# ep_project_1.net
KiCad netlist of a schematic drawn in EAGLE
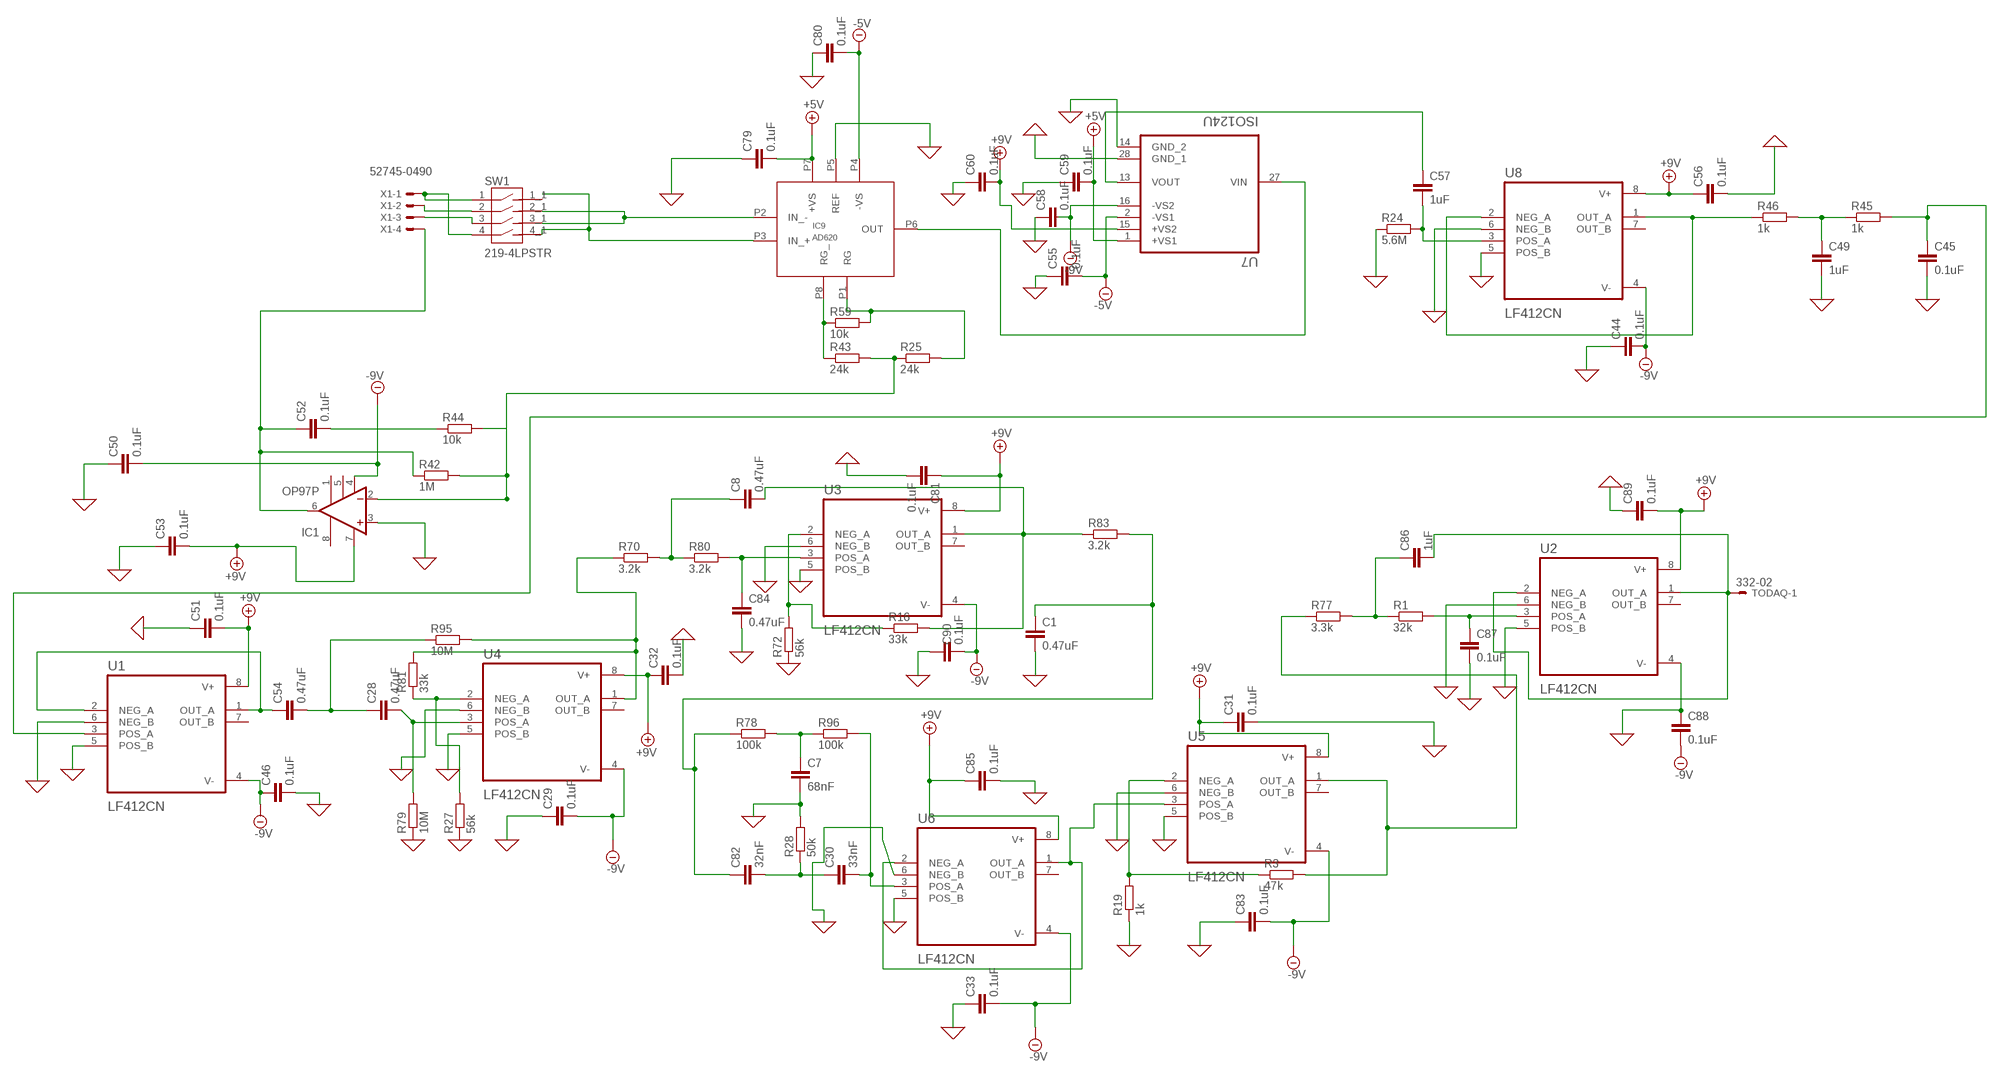
[diagram p0: schematic, sheet 1]

(export (version "E")
  (design (tool "Eeschema 10.0.6"))
  (components
    (comp (ref "C1")
      (value "0.47uF")
      (footprint "eagle-import:C025-025X050")
      (libsource (lib "eagle-import") (part "C-EU025-025X050"))
    )
    (comp (ref "C7")
      (value "68nF")
      (footprint "eagle-import:C025-025X050")
      (libsource (lib "eagle-import") (part "C-EU025-025X050"))
    )
    (comp (ref "C8")
      (value "0.47uF")
      (footprint "eagle-import:C025-025X050")
      (libsource (lib "eagle-import") (part "C-EU025-025X050"))
    )
    (comp (ref "C28")
      (value "0.47uF")
      (footprint "eagle-import:C025-025X050")
      (libsource (lib "eagle-import") (part "C-EU025-025X050"))
    )
    (comp (ref "C29")
      (value "0.1uF")
      (footprint "eagle-import:C025-025X050")
      (libsource (lib "eagle-import") (part "C-EU025-025X050"))
    )
    (comp (ref "C30")
      (value "33nF")
      (footprint "eagle-import:C025-025X050")
      (libsource (lib "eagle-import") (part "C-EU025-025X050"))
    )
    (comp (ref "C31")
      (value "0.1uF")
      (footprint "eagle-import:C025-025X050")
      (libsource (lib "eagle-import") (part "C-EU025-025X050"))
    )
    (comp (ref "C32")
      (value "0.1uF")
      (footprint "eagle-import:C025-025X050")
      (libsource (lib "eagle-import") (part "C-EU025-025X050"))
    )
    (comp (ref "C33")
      (value "0.1uF")
      (footprint "eagle-import:C025-025X050")
      (libsource (lib "eagle-import") (part "C-EU025-025X050"))
    )
    (comp (ref "C44")
      (value "0.1uF")
      (footprint "eagle-import:C025-025X050")
      (libsource (lib "eagle-import") (part "C-EU025-025X050"))
    )
    (comp (ref "C45")
      (value "0.1uF")
      (footprint "eagle-import:C025-025X050")
      (libsource (lib "eagle-import") (part "C-EU025-025X050"))
    )
    (comp (ref "C46")
      (value "0.1uF")
      (footprint "eagle-import:C025-025X050")
      (libsource (lib "eagle-import") (part "C-EU025-025X050"))
    )
    (comp (ref "C49")
      (value "1uF")
      (footprint "eagle-import:C025-025X050")
      (libsource (lib "eagle-import") (part "C-EU025-025X050"))
    )
    (comp (ref "C50")
      (value "0.1uF")
      (footprint "eagle-import:C025-025X050")
      (libsource (lib "eagle-import") (part "C-EU025-025X050"))
    )
    (comp (ref "C51")
      (value "0.1uF")
      (footprint "eagle-import:C025-025X050")
      (libsource (lib "eagle-import") (part "C-EU025-025X050"))
    )
    (comp (ref "C52")
      (value "0.1uF")
      (footprint "eagle-import:C025-025X050")
      (libsource (lib "eagle-import") (part "C-EU025-025X050"))
    )
    (comp (ref "C53")
      (value "0.1uF")
      (footprint "eagle-import:C025-025X050")
      (libsource (lib "eagle-import") (part "C-EU025-025X050"))
    )
    (comp (ref "C54")
      (value "0.47uF")
      (footprint "eagle-import:C025-025X050")
      (libsource (lib "eagle-import") (part "C-EU025-025X050"))
    )
    (comp (ref "C55")
      (value "0.1uF")
      (footprint "eagle-import:C025-025X050")
      (libsource (lib "eagle-import") (part "C-EU025-025X050"))
    )
    (comp (ref "C56")
      (value "0.1uF")
      (footprint "eagle-import:C025-025X050")
      (libsource (lib "eagle-import") (part "C-EU025-025X050"))
    )
    (comp (ref "C57")
      (value "1uF")
      (footprint "eagle-import:C025-025X050")
      (libsource (lib "eagle-import") (part "C-EU025-025X050"))
    )
    (comp (ref "C58")
      (value "0.1uF")
      (footprint "eagle-import:C025-025X050")
      (libsource (lib "eagle-import") (part "C-EU025-025X050"))
    )
    (comp (ref "C59")
      (value "0.1uF")
      (footprint "eagle-import:C025-025X050")
      (libsource (lib "eagle-import") (part "C-EU025-025X050"))
    )
    (comp (ref "C60")
      (value "0.1uF")
      (footprint "eagle-import:C025-025X050")
      (libsource (lib "eagle-import") (part "C-EU025-025X050"))
    )
    (comp (ref "C79")
      (value "0.1uF")
      (footprint "eagle-import:C025-025X050")
      (libsource (lib "eagle-import") (part "C-EU025-025X050"))
    )
    (comp (ref "C80")
      (value "0.1uF")
      (footprint "eagle-import:C025-025X050")
      (libsource (lib "eagle-import") (part "C-EU025-025X050"))
    )
    (comp (ref "C81")
      (value "0.1uF")
      (footprint "eagle-import:C025-025X050")
      (libsource (lib "eagle-import") (part "C-EU025-025X050"))
    )
    (comp (ref "C82")
      (value "32nF")
      (footprint "eagle-import:C025-025X050")
      (libsource (lib "eagle-import") (part "C-EU025-025X050"))
    )
    (comp (ref "C83")
      (value "0.1uF")
      (footprint "eagle-import:C025-025X050")
      (libsource (lib "eagle-import") (part "C-EU025-025X050"))
    )
    (comp (ref "C84")
      (value "0.47uF")
      (footprint "eagle-import:C025-025X050")
      (libsource (lib "eagle-import") (part "C-EU025-025X050"))
    )
    (comp (ref "C85")
      (value "0.1uF")
      (footprint "eagle-import:C025-025X050")
      (libsource (lib "eagle-import") (part "C-EU025-025X050"))
    )
    (comp (ref "C86")
      (value "1uF")
      (footprint "eagle-import:C025-025X050")
      (libsource (lib "eagle-import") (part "C-EU025-025X050"))
    )
    (comp (ref "C87")
      (value "0.1uF")
      (footprint "eagle-import:C025-025X050")
      (libsource (lib "eagle-import") (part "C-EU025-025X050"))
    )
    (comp (ref "C88")
      (value "0.1uF")
      (footprint "eagle-import:C025-025X050")
      (libsource (lib "eagle-import") (part "C-EU025-025X050"))
    )
    (comp (ref "C89")
      (value "0.1uF")
      (footprint "eagle-import:C025-025X050")
      (libsource (lib "eagle-import") (part "C-EU025-025X050"))
    )
    (comp (ref "C90")
      (value "0.1uF")
      (footprint "eagle-import:C025-025X050")
      (libsource (lib "eagle-import") (part "C-EU025-025X050"))
    )
    (comp (ref "IC1")
      (value "OP97P")
      (footprint "eagle-import:DIL08")
      (libsource (lib "eagle-import") (part "OP97P"))
    )
    (comp (ref "IC9")
      (value "AD620")
      (footprint "eagle-import:DIL8")
      (libsource (lib "eagle-import") (part "AD620"))
    )
    (comp (ref "R1")
      (value "32k")
      (footprint "eagle-import:0204_7")
      (libsource (lib "eagle-import") (part "R-EU_0204/7"))
    )
    (comp (ref "R3")
      (value "47k")
      (footprint "eagle-import:0204_7")
      (libsource (lib "eagle-import") (part "R-EU_0204/7"))
    )
    (comp (ref "R16")
      (value "33k")
      (footprint "eagle-import:VTA55")
      (libsource (lib "eagle-import") (part "R-EU_VTA55"))
    )
    (comp (ref "R19")
      (value "1k")
      (footprint "eagle-import:0204_7")
      (libsource (lib "eagle-import") (part "R-EU_0204/7"))
    )
    (comp (ref "R24")
      (value "5.6M")
      (footprint "eagle-import:0204_7")
      (libsource (lib "eagle-import") (part "R-EU_0204/7"))
    )
    (comp (ref "R25")
      (value "24k")
      (footprint "eagle-import:0204_7")
      (libsource (lib "eagle-import") (part "R-EU_0204/7"))
    )
    (comp (ref "R27")
      (value "56k")
      (footprint "eagle-import:0204_7")
      (libsource (lib "eagle-import") (part "R-EU_0204/7"))
    )
    (comp (ref "R28")
      (value "50k")
      (footprint "eagle-import:0204_7")
      (libsource (lib "eagle-import") (part "R-EU_0204/7"))
    )
    (comp (ref "R42")
      (value "1M")
      (footprint "eagle-import:0204_7")
      (libsource (lib "eagle-import") (part "R-EU_0204/7"))
    )
    (comp (ref "R43")
      (value "24k")
      (footprint "eagle-import:0204_7")
      (libsource (lib "eagle-import") (part "R-EU_0204/7"))
    )
    (comp (ref "R44")
      (value "10k")
      (footprint "eagle-import:0204_7")
      (libsource (lib "eagle-import") (part "R-EU_0204/7"))
    )
    (comp (ref "R45")
      (value "1k")
      (footprint "eagle-import:0204_7")
      (libsource (lib "eagle-import") (part "R-EU_0204/7"))
    )
    (comp (ref "R46")
      (value "1k")
      (footprint "eagle-import:0204_7")
      (libsource (lib "eagle-import") (part "R-EU_0204/7"))
    )
    (comp (ref "R59")
      (value "10k")
      (footprint "eagle-import:0204_7")
      (libsource (lib "eagle-import") (part "R-EU_0204/7"))
    )
    (comp (ref "R70")
      (value "3.2k")
      (footprint "eagle-import:0204_7")
      (libsource (lib "eagle-import") (part "R-EU_0204/7"))
    )
    (comp (ref "R72")
      (value "56k")
      (footprint "eagle-import:0204_7")
      (libsource (lib "eagle-import") (part "R-EU_0204/7"))
    )
    (comp (ref "R77")
      (value "3.3k")
      (footprint "eagle-import:0204_7")
      (libsource (lib "eagle-import") (part "R-EU_0204/7"))
    )
    (comp (ref "R78")
      (value "100k")
      (footprint "eagle-import:0204_7")
      (libsource (lib "eagle-import") (part "R-EU_0204/7"))
    )
    (comp (ref "R79")
      (value "10M")
      (footprint "eagle-import:0204_7")
      (libsource (lib "eagle-import") (part "R-EU_0204/7"))
    )
    (comp (ref "R80")
      (value "3.2k")
      (footprint "eagle-import:0204_7")
      (libsource (lib "eagle-import") (part "R-EU_0204/7"))
    )
    (comp (ref "R81")
      (value "33k")
      (footprint "eagle-import:0204_7")
      (libsource (lib "eagle-import") (part "R-EU_0204/7"))
    )
    (comp (ref "R83")
      (value "3.2k")
      (footprint "eagle-import:0204_7")
      (libsource (lib "eagle-import") (part "R-EU_0204/7"))
    )
    (comp (ref "R95")
      (value "10M")
      (footprint "eagle-import:0204_7")
      (libsource (lib "eagle-import") (part "R-EU_0204/7"))
    )
    (comp (ref "R96")
      (value "100k")
      (footprint "eagle-import:0204_7")
      (libsource (lib "eagle-import") (part "R-EU_0204/7"))
    )
    (comp (ref "SW1")
      (value "219-4LPSTR")
      (footprint "eagle-import:SW_219-4LPSTR")
      (fields (field (name "MF") "CTS Electrocomponents"))
      (libsource (lib "eagle-import") (part "219-4LPSTR"))
    )
    (comp (ref "TODAQ")
      (value "332-02")
      (footprint "eagle-import:332-02")
      (libsource (lib "eagle-import") (part "332-02"))
    )
    (comp (ref "U1")
      (value "LF412CN")
      (footprint "eagle-import:DIP794W45P254L959H508Q8")
      (fields (field (name "MF") "Texas Instruments"))
      (libsource (lib "eagle-import") (part "LF412CN"))
    )
    (comp (ref "U2")
      (value "LF412CN")
      (footprint "eagle-import:DIP794W45P254L959H508Q8")
      (fields (field (name "MF") "Texas Instruments"))
      (libsource (lib "eagle-import") (part "LF412CN"))
    )
    (comp (ref "U3")
      (value "LF412CN")
      (footprint "eagle-import:DIP794W45P254L959H508Q8")
      (fields (field (name "MF") "Texas Instruments"))
      (libsource (lib "eagle-import") (part "LF412CN"))
    )
    (comp (ref "U4")
      (value "LF412CN")
      (footprint "eagle-import:DIP794W45P254L959H508Q8")
      (fields (field (name "MF") "Texas Instruments"))
      (libsource (lib "eagle-import") (part "LF412CN"))
    )
    (comp (ref "U5")
      (value "LF412CN")
      (footprint "eagle-import:DIP794W45P254L959H508Q8")
      (fields (field (name "MF") "Texas Instruments"))
      (libsource (lib "eagle-import") (part "LF412CN"))
    )
    (comp (ref "U6")
      (value "LF412CN")
      (footprint "eagle-import:DIP794W45P254L959H508Q8")
      (fields (field (name "MF") "Texas Instruments"))
      (libsource (lib "eagle-import") (part "LF412CN"))
    )
    (comp (ref "U7")
      (value "ISO124U")
      (footprint "eagle-import:SOIC127P1033X265-8N")
      (fields (field (name "MF") "Texas Instruments"))
      (libsource (lib "eagle-import") (part "ISO124U"))
    )
    (comp (ref "U8")
      (value "LF412CN")
      (footprint "eagle-import:DIP794W45P254L959H508Q8")
      (fields (field (name "MF") "Texas Instruments"))
      (libsource (lib "eagle-import") (part "LF412CN"))
    )
    (comp (ref "X1")
      (value "52745-0490")
      (footprint "eagle-import:52745-0490")
      (fields (field (name "MF") "MOLEX"))
      (libsource (lib "eagle-import") (part "52745-0490"))
    )
  )
  (nets
    (net (code "1") (name "+5V") (class "Default")
      (node (ref "C59") (pin "2") (pinfunction "2_2") (pintype "passive"))
      (node (ref "C79") (pin "2") (pinfunction "2_2") (pintype "passive"))
      (node (ref "IC9") (pin "P7") (pinfunction "+VS_P7") (pintype "power_in"))
      (node (ref "U7") (pin "1") (pinfunction "+VS1_1") (pintype "power_in"))
    )
    (net (code "2") (name "+9V") (class "Default")
      (node (ref "C31") (pin "1") (pinfunction "1_1") (pintype "passive"))
      (node (ref "C32") (pin "1") (pinfunction "1_1") (pintype "passive"))
      (node (ref "C51") (pin "2") (pinfunction "2_2") (pintype "passive"))
      (node (ref "C53") (pin "2") (pinfunction "2_2") (pintype "passive"))
      (node (ref "C56") (pin "1") (pinfunction "1_1") (pintype "passive"))
      (node (ref "C60") (pin "2") (pinfunction "2_2") (pintype "passive"))
      (node (ref "C81") (pin "1") (pinfunction "1_1") (pintype "passive"))
      (node (ref "C85") (pin "1") (pinfunction "1_1") (pintype "passive"))
      (node (ref "C89") (pin "2") (pinfunction "2_2") (pintype "passive"))
      (node (ref "IC1") (pin "7") (pinfunction "V+_7") (pintype "power_in"))
      (node (ref "U1") (pin "8") (pinfunction "V+_8") (pintype "power_in"))
      (node (ref "U2") (pin "8") (pinfunction "V+_8") (pintype "power_in"))
      (node (ref "U3") (pin "8") (pinfunction "V+_8") (pintype "power_in"))
      (node (ref "U4") (pin "8") (pinfunction "V+_8") (pintype "power_in"))
      (node (ref "U5") (pin "8") (pinfunction "V+_8") (pintype "power_in"))
      (node (ref "U6") (pin "8") (pinfunction "V+_8") (pintype "power_in"))
      (node (ref "U7") (pin "15") (pinfunction "+VS2_15") (pintype "power_in"))
      (node (ref "U8") (pin "8") (pinfunction "V+_8") (pintype "power_in"))
    )
    (net (code "3") (name "-5V") (class "Default")
      (node (ref "C55") (pin "2") (pinfunction "2_2") (pintype "passive"))
      (node (ref "C80") (pin "2") (pinfunction "2_2") (pintype "passive"))
      (node (ref "IC9") (pin "P4") (pinfunction "-VS_P4") (pintype "power_in"))
      (node (ref "U7") (pin "2") (pinfunction "-VS1_2") (pintype "power_in"))
    )
    (net (code "4") (name "-9V") (class "Default")
      (node (ref "C29") (pin "2") (pinfunction "2_2") (pintype "passive"))
      (node (ref "C33") (pin "2") (pinfunction "2_2") (pintype "passive"))
      (node (ref "C44") (pin "2") (pinfunction "2_2") (pintype "passive"))
      (node (ref "C46") (pin "1") (pinfunction "1_1") (pintype "passive"))
      (node (ref "C50") (pin "2") (pinfunction "2_2") (pintype "passive"))
      (node (ref "C58") (pin "2") (pinfunction "2_2") (pintype "passive"))
      (node (ref "C83") (pin "2") (pinfunction "2_2") (pintype "passive"))
      (node (ref "C88") (pin "2") (pinfunction "2_2") (pintype "passive"))
      (node (ref "C90") (pin "2") (pinfunction "2_2") (pintype "passive"))
      (node (ref "IC1") (pin "4") (pinfunction "V-_4") (pintype "power_in"))
      (node (ref "U1") (pin "4") (pinfunction "V-_4") (pintype "power_in"))
      (node (ref "U3") (pin "4") (pinfunction "V-_4") (pintype "power_in"))
      (node (ref "U4") (pin "4") (pinfunction "V-_4") (pintype "power_in"))
      (node (ref "U5") (pin "4") (pinfunction "V-_4") (pintype "power_in"))
      (node (ref "U6") (pin "4") (pinfunction "V-_4") (pintype "power_in"))
      (node (ref "U7") (pin "16") (pinfunction "-VS2_16") (pintype "power_in"))
      (node (ref "U8") (pin "4") (pinfunction "V-_4") (pintype "power_in"))
    )
    (net (code "5") (name "0") (class "Default")
      (node (ref "C1") (pin "2") (pinfunction "2_2") (pintype "passive"))
      (node (ref "C29") (pin "1") (pinfunction "1_1") (pintype "passive"))
      (node (ref "C31") (pin "2") (pinfunction "2_2") (pintype "passive"))
      (node (ref "C32") (pin "2") (pinfunction "2_2") (pintype "passive"))
      (node (ref "C33") (pin "1") (pinfunction "1_1") (pintype "passive"))
      (node (ref "C44") (pin "1") (pinfunction "1_1") (pintype "passive"))
      (node (ref "C45") (pin "2") (pinfunction "2_2") (pintype "passive"))
      (node (ref "C46") (pin "2") (pinfunction "2_2") (pintype "passive"))
      (node (ref "C49") (pin "2") (pinfunction "2_2") (pintype "passive"))
      (node (ref "C50") (pin "1") (pinfunction "1_1") (pintype "passive"))
      (node (ref "C51") (pin "1") (pinfunction "1_1") (pintype "passive"))
      (node (ref "C53") (pin "1") (pinfunction "1_1") (pintype "passive"))
      (node (ref "C55") (pin "1") (pinfunction "1_1") (pintype "passive"))
      (node (ref "C56") (pin "2") (pinfunction "2_2") (pintype "passive"))
      (node (ref "C58") (pin "1") (pinfunction "1_1") (pintype "passive"))
      (node (ref "C59") (pin "1") (pinfunction "1_1") (pintype "passive"))
      (node (ref "C60") (pin "1") (pinfunction "1_1") (pintype "passive"))
      (node (ref "C7") (pin "2") (pinfunction "2_2") (pintype "passive"))
      (node (ref "C79") (pin "1") (pinfunction "1_1") (pintype "passive"))
      (node (ref "C80") (pin "1") (pinfunction "1_1") (pintype "passive"))
      (node (ref "C81") (pin "2") (pinfunction "2_2") (pintype "passive"))
      (node (ref "C83") (pin "1") (pinfunction "1_1") (pintype "passive"))
      (node (ref "C84") (pin "2") (pinfunction "2_2") (pintype "passive"))
      (node (ref "C85") (pin "2") (pinfunction "2_2") (pintype "passive"))
      (node (ref "C87") (pin "2") (pinfunction "2_2") (pintype "passive"))
      (node (ref "C88") (pin "1") (pinfunction "1_1") (pintype "passive"))
      (node (ref "C89") (pin "1") (pinfunction "1_1") (pintype "passive"))
      (node (ref "C90") (pin "1") (pinfunction "1_1") (pintype "passive"))
      (node (ref "IC1") (pin "3") (pinfunction "+IN_3") (pintype "input"))
      (node (ref "IC9") (pin "P5") (pinfunction "REF_P5") (pintype "power_in"))
      (node (ref "R19") (pin "1") (pinfunction "1_1") (pintype "passive"))
      (node (ref "R24") (pin "1") (pinfunction "1_1") (pintype "passive"))
      (node (ref "R27") (pin "1") (pinfunction "1_1") (pintype "passive"))
      (node (ref "R28") (pin "2") (pinfunction "2_2") (pintype "passive"))
      (node (ref "R72") (pin "1") (pinfunction "1_1") (pintype "passive"))
      (node (ref "R79") (pin "1") (pinfunction "1_1") (pintype "passive"))
      (node (ref "U1") (pin "5") (pinfunction "POS_B_5") (pintype "input"))
      (node (ref "U1") (pin "6") (pinfunction "NEG_B_6") (pintype "input"))
      (node (ref "U2") (pin "4") (pinfunction "V-_4") (pintype "power_in"))
      (node (ref "U2") (pin "5") (pinfunction "POS_B_5") (pintype "input"))
      (node (ref "U2") (pin "6") (pinfunction "NEG_B_6") (pintype "input"))
      (node (ref "U3") (pin "5") (pinfunction "POS_B_5") (pintype "input"))
      (node (ref "U3") (pin "6") (pinfunction "NEG_B_6") (pintype "input"))
      (node (ref "U4") (pin "5") (pinfunction "POS_B_5") (pintype "input"))
      (node (ref "U4") (pin "6") (pinfunction "NEG_B_6") (pintype "input"))
      (node (ref "U5") (pin "5") (pinfunction "POS_B_5") (pintype "input"))
      (node (ref "U5") (pin "6") (pinfunction "NEG_B_6") (pintype "input"))
      (node (ref "U6") (pin "5") (pinfunction "POS_B_5") (pintype "input"))
      (node (ref "U6") (pin "6") (pinfunction "NEG_B_6") (pintype "input"))
      (node (ref "U7") (pin "14") (pinfunction "GND_2_14") (pintype "power_in"))
      (node (ref "U7") (pin "28") (pinfunction "GND_1_28") (pintype "power_in"))
      (node (ref "U8") (pin "5") (pinfunction "POS_B_5") (pintype "input"))
      (node (ref "U8") (pin "6") (pinfunction "NEG_B_6") (pintype "input"))
    )
    (net (code "6") (name "Net-(C1-Pad1)") (class "Default")
      (node (ref "C1") (pin "1") (pinfunction "1_1") (pintype "passive"))
      (node (ref "C82") (pin "1") (pinfunction "1_1") (pintype "passive"))
      (node (ref "R78") (pin "1") (pinfunction "1_1") (pintype "passive"))
      (node (ref "R83") (pin "2") (pinfunction "2_2") (pintype "passive"))
    )
    (net (code "7") (name "Net-(C7-Pad1)") (class "Default")
      (node (ref "C7") (pin "1") (pinfunction "1_1") (pintype "passive"))
      (node (ref "R78") (pin "2") (pinfunction "2_2") (pintype "passive"))
      (node (ref "R96") (pin "1") (pinfunction "1_1") (pintype "passive"))
    )
    (net (code "8") (name "Net-(C8-Pad1)") (class "Default")
      (node (ref "C8") (pin "1") (pinfunction "1_1") (pintype "passive"))
      (node (ref "R70") (pin "2") (pinfunction "2_2") (pintype "passive"))
      (node (ref "R80") (pin "1") (pinfunction "1_1") (pintype "passive"))
    )
    (net (code "9") (name "Net-(C28-Pad1)") (class "Default")
      (node (ref "C28") (pin "1") (pinfunction "1_1") (pintype "passive"))
      (node (ref "C54") (pin "2") (pinfunction "2_2") (pintype "passive"))
      (node (ref "R95") (pin "1") (pinfunction "1_1") (pintype "passive"))
    )
    (net (code "10") (name "Net-(C30-Pad1)") (class "Default")
      (node (ref "C30") (pin "1") (pinfunction "1_1") (pintype "passive"))
      (node (ref "C82") (pin "2") (pinfunction "2_2") (pintype "passive"))
      (node (ref "R28") (pin "1") (pinfunction "1_1") (pintype "passive"))
    )
    (net (code "11") (name "Net-(C49-Pad1)") (class "Default")
      (node (ref "C49") (pin "1") (pinfunction "1_1") (pintype "passive"))
      (node (ref "R45") (pin "1") (pinfunction "1_1") (pintype "passive"))
      (node (ref "R46") (pin "2") (pinfunction "2_2") (pintype "passive"))
    )
    (net (code "12") (name "Net-(C52-Pad2)") (class "Default")
      (node (ref "C52") (pin "2") (pinfunction "2_2") (pintype "passive"))
      (node (ref "R44") (pin "1") (pinfunction "1_1") (pintype "passive"))
    )
    (net (code "13") (name "Net-(C86-Pad1)") (class "Default")
      (node (ref "C86") (pin "1") (pinfunction "1_1") (pintype "passive"))
      (node (ref "R1") (pin "1") (pinfunction "1_1") (pintype "passive"))
      (node (ref "R77") (pin "2") (pinfunction "2_2") (pintype "passive"))
    )
    (net (code "14") (name "Net-(IC1--IN)") (class "Default")
      (node (ref "IC1") (pin "2") (pinfunction "-IN_2") (pintype "input"))
      (node (ref "R25") (pin "1") (pinfunction "1_1") (pintype "passive"))
      (node (ref "R42") (pin "2") (pinfunction "2_2") (pintype "passive"))
      (node (ref "R43") (pin "2") (pinfunction "2_2") (pintype "passive"))
      (node (ref "R44") (pin "2") (pinfunction "2_2") (pintype "passive"))
    )
    (net (code "15") (name "Net-(IC1-OUT)") (class "Default")
      (node (ref "C52") (pin "1") (pinfunction "1_1") (pintype "passive"))
      (node (ref "IC1") (pin "6") (pinfunction "OUT_6") (pintype "output"))
      (node (ref "R42") (pin "1") (pinfunction "1_1") (pintype "passive"))
      (node (ref "X1") (pin "4") (pinfunction "S_4") (pintype "passive"))
    )
    (net (code "16") (name "Net-(IC9-IN_+)") (class "Default")
      (node (ref "IC9") (pin "P3") (pinfunction "IN_+_P3") (pintype "input"))
      (node (ref "SW1") (pin "4_1") (pinfunction "4_1_4_1") (pintype "passive"))
    )
    (net (code "17") (name "Net-(IC9-IN_-)") (class "Default")
      (node (ref "IC9") (pin "P2") (pinfunction "IN_-_P2") (pintype "input"))
      (node (ref "SW1") (pin "2_1") (pinfunction "2_1_2_1") (pintype "passive"))
      (node (ref "SW1") (pin "3_1") (pinfunction "3_1_3_1") (pintype "passive"))
    )
    (net (code "18") (name "Net-(IC9-OUT)") (class "Default")
      (node (ref "IC9") (pin "P6") (pinfunction "OUT_P6") (pintype "output"))
      (node (ref "U7") (pin "27") (pinfunction "VIN_27") (pintype "input"))
    )
    (net (code "19") (name "Net-(IC9-RG)") (class "Default")
      (node (ref "IC9") (pin "P1") (pinfunction "RG_P1") (pintype "input"))
      (node (ref "R25") (pin "2") (pinfunction "2_2") (pintype "passive"))
      (node (ref "R59") (pin "2") (pinfunction "2_2") (pintype "passive"))
    )
    (net (code "20") (name "Net-(IC9-RG_)") (class "Default")
      (node (ref "IC9") (pin "P8") (pinfunction "RG__P8") (pintype "input"))
      (node (ref "R43") (pin "1") (pinfunction "1_1") (pintype "passive"))
      (node (ref "R59") (pin "1") (pinfunction "1_1") (pintype "passive"))
    )
    (net (code "21") (name "Net-(TODAQA-S)") (class "Default")
      (node (ref "C86") (pin "2") (pinfunction "2_2") (pintype "passive"))
      (node (ref "TODAQ") (pin "1") (pinfunction "S_1") (pintype "passive"))
      (node (ref "U2") (pin "1") (pinfunction "OUT_A_1") (pintype "output"))
      (node (ref "U2") (pin "2") (pinfunction "NEG_A_2") (pintype "input"))
    )
    (net (code "22") (name "Net-(U1-NEG_A)") (class "Default")
      (node (ref "C54") (pin "1") (pinfunction "1_1") (pintype "passive"))
      (node (ref "U1") (pin "1") (pinfunction "OUT_A_1") (pintype "output"))
      (node (ref "U1") (pin "2") (pinfunction "NEG_A_2") (pintype "input"))
    )
    (net (code "23") (name "Net-(U1-POS_A)") (class "Default")
      (node (ref "C45") (pin "1") (pinfunction "1_1") (pintype "passive"))
      (node (ref "R45") (pin "2") (pinfunction "2_2") (pintype "passive"))
      (node (ref "U1") (pin "3") (pinfunction "POS_A_3") (pintype "input"))
    )
    (net (code "24") (name "Net-(U2-POS_A)") (class "Default")
      (node (ref "C87") (pin "1") (pinfunction "1_1") (pintype "passive"))
      (node (ref "R1") (pin "2") (pinfunction "2_2") (pintype "passive"))
      (node (ref "U2") (pin "3") (pinfunction "POS_A_3") (pintype "input"))
    )
    (net (code "25") (name "Net-(U3-NEG_A)") (class "Default")
      (node (ref "R16") (pin "1") (pinfunction "1_1") (pintype "passive"))
      (node (ref "R72") (pin "2") (pinfunction "2_2") (pintype "passive"))
      (node (ref "U3") (pin "2") (pinfunction "NEG_A_2") (pintype "input"))
    )
    (net (code "26") (name "Net-(U3-OUT_A)") (class "Default")
      (node (ref "C8") (pin "2") (pinfunction "2_2") (pintype "passive"))
      (node (ref "R16") (pin "2") (pinfunction "2_2") (pintype "passive"))
      (node (ref "R83") (pin "1") (pinfunction "1_1") (pintype "passive"))
      (node (ref "U3") (pin "1") (pinfunction "OUT_A_1") (pintype "output"))
    )
    (net (code "27") (name "Net-(U3-POS_A)") (class "Default")
      (node (ref "C84") (pin "1") (pinfunction "1_1") (pintype "passive"))
      (node (ref "R80") (pin "2") (pinfunction "2_2") (pintype "passive"))
      (node (ref "U3") (pin "3") (pinfunction "POS_A_3") (pintype "input"))
    )
    (net (code "28") (name "Net-(U4-NEG_A)") (class "Default")
      (node (ref "R27") (pin "2") (pinfunction "2_2") (pintype "passive"))
      (node (ref "R81") (pin "1") (pinfunction "1_1") (pintype "passive"))
      (node (ref "U4") (pin "2") (pinfunction "NEG_A_2") (pintype "input"))
    )
    (net (code "29") (name "Net-(U4-OUT_A)") (class "Default")
      (node (ref "R70") (pin "1") (pinfunction "1_1") (pintype "passive"))
      (node (ref "R81") (pin "2") (pinfunction "2_2") (pintype "passive"))
      (node (ref "R95") (pin "2") (pinfunction "2_2") (pintype "passive"))
      (node (ref "U4") (pin "1") (pinfunction "OUT_A_1") (pintype "output"))
    )
    (net (code "30") (name "Net-(U4-POS_A)") (class "Default")
      (node (ref "C28") (pin "2") (pinfunction "2_2") (pintype "passive"))
      (node (ref "R79") (pin "2") (pinfunction "2_2") (pintype "passive"))
      (node (ref "U4") (pin "3") (pinfunction "POS_A_3") (pintype "input"))
    )
    (net (code "31") (name "Net-(U5-NEG_A)") (class "Default")
      (node (ref "R19") (pin "2") (pinfunction "2_2") (pintype "passive"))
      (node (ref "R3") (pin "1") (pinfunction "1_1") (pintype "passive"))
      (node (ref "U5") (pin "2") (pinfunction "NEG_A_2") (pintype "input"))
    )
    (net (code "32") (name "Net-(U5-OUT_A)") (class "Default")
      (node (ref "R3") (pin "2") (pinfunction "2_2") (pintype "passive"))
      (node (ref "R77") (pin "1") (pinfunction "1_1") (pintype "passive"))
      (node (ref "U5") (pin "1") (pinfunction "OUT_A_1") (pintype "output"))
    )
    (net (code "33") (name "Net-(U5-POS_A)") (class "Default")
      (node (ref "U5") (pin "3") (pinfunction "POS_A_3") (pintype "input"))
      (node (ref "U6") (pin "1") (pinfunction "OUT_A_1") (pintype "output"))
      (node (ref "U6") (pin "2") (pinfunction "NEG_A_2") (pintype "input"))
    )
    (net (code "34") (name "Net-(U6-POS_A)") (class "Default")
      (node (ref "C30") (pin "2") (pinfunction "2_2") (pintype "passive"))
      (node (ref "R96") (pin "2") (pinfunction "2_2") (pintype "passive"))
      (node (ref "U6") (pin "3") (pinfunction "POS_A_3") (pintype "input"))
    )
    (net (code "35") (name "Net-(U7-VOUT)") (class "Default")
      (node (ref "C57") (pin "1") (pinfunction "1_1") (pintype "passive"))
      (node (ref "U7") (pin "13") (pinfunction "VOUT_13") (pintype "output"))
    )
    (net (code "36") (name "Net-(U8-NEG_A)") (class "Default")
      (node (ref "R46") (pin "1") (pinfunction "1_1") (pintype "passive"))
      (node (ref "U8") (pin "1") (pinfunction "OUT_A_1") (pintype "output"))
      (node (ref "U8") (pin "2") (pinfunction "NEG_A_2") (pintype "input"))
    )
    (net (code "37") (name "Net-(U8-POS_A)") (class "Default")
      (node (ref "C57") (pin "2") (pinfunction "2_2") (pintype "passive"))
      (node (ref "R24") (pin "2") (pinfunction "2_2") (pintype "passive"))
      (node (ref "U8") (pin "3") (pinfunction "POS_A_3") (pintype "input"))
    )
    (net (code "38") (name "Net-(X1A-S)") (class "Default")
      (node (ref "SW1") (pin "1") (pinfunction "1_1") (pintype "passive"))
      (node (ref "SW1") (pin "4") (pinfunction "4_4") (pintype "passive"))
      (node (ref "X1") (pin "1") (pinfunction "S_1") (pintype "passive"))
    )
    (net (code "39") (name "Net-(X1B-S)") (class "Default")
      (node (ref "SW1") (pin "2") (pinfunction "2_2") (pintype "passive"))
      (node (ref "X1") (pin "2") (pinfunction "S_2") (pintype "passive"))
    )
    (net (code "40") (name "Net-(X1C-S)") (class "Default")
      (node (ref "SW1") (pin "3") (pinfunction "3_3") (pintype "passive"))
      (node (ref "X1") (pin "3") (pinfunction "S_3") (pintype "passive"))
    )
    (net (code "41") (name "unconnected-(IC1-BAL1-Pad1)") (class "Default")
      (node (ref "IC1") (pin "1") (pinfunction "BAL1_1") (pintype "passive"))
    )
    (net (code "42") (name "unconnected-(IC1-BAL2-Pad8)") (class "Default")
      (node (ref "IC1") (pin "8") (pinfunction "BAL2_8") (pintype "passive"))
    )
    (net (code "43") (name "unconnected-(IC1-COMP-Pad5)") (class "Default")
      (node (ref "IC1") (pin "5") (pinfunction "COMP_5") (pintype "passive"))
    )
    (net (code "44") (name "unconnected-(SW1-Pad1_1)") (class "Default")
      (node (ref "SW1") (pin "1_1") (pinfunction "1_1_1_1") (pintype "passive"))
    )
    (net (code "45") (name "unconnected-(U1-OUT_B-Pad7)") (class "Default")
      (node (ref "U1") (pin "7") (pinfunction "OUT_B_7") (pintype "output"))
    )
    (net (code "46") (name "unconnected-(U2-OUT_B-Pad7)") (class "Default")
      (node (ref "U2") (pin "7") (pinfunction "OUT_B_7") (pintype "output"))
    )
    (net (code "47") (name "unconnected-(U3-OUT_B-Pad7)") (class "Default")
      (node (ref "U3") (pin "7") (pinfunction "OUT_B_7") (pintype "output"))
    )
    (net (code "48") (name "unconnected-(U4-OUT_B-Pad7)") (class "Default")
      (node (ref "U4") (pin "7") (pinfunction "OUT_B_7") (pintype "output"))
    )
    (net (code "49") (name "unconnected-(U5-OUT_B-Pad7)") (class "Default")
      (node (ref "U5") (pin "7") (pinfunction "OUT_B_7") (pintype "output"))
    )
    (net (code "50") (name "unconnected-(U6-OUT_B-Pad7)") (class "Default")
      (node (ref "U6") (pin "7") (pinfunction "OUT_B_7") (pintype "output"))
    )
    (net (code "51") (name "unconnected-(U8-OUT_B-Pad7)") (class "Default")
      (node (ref "U8") (pin "7") (pinfunction "OUT_B_7") (pintype "output"))
    )
  )
)
